# JDM2_w_MOSFET_2.net
KiCad netlist of a schematic drawn in EAGLE
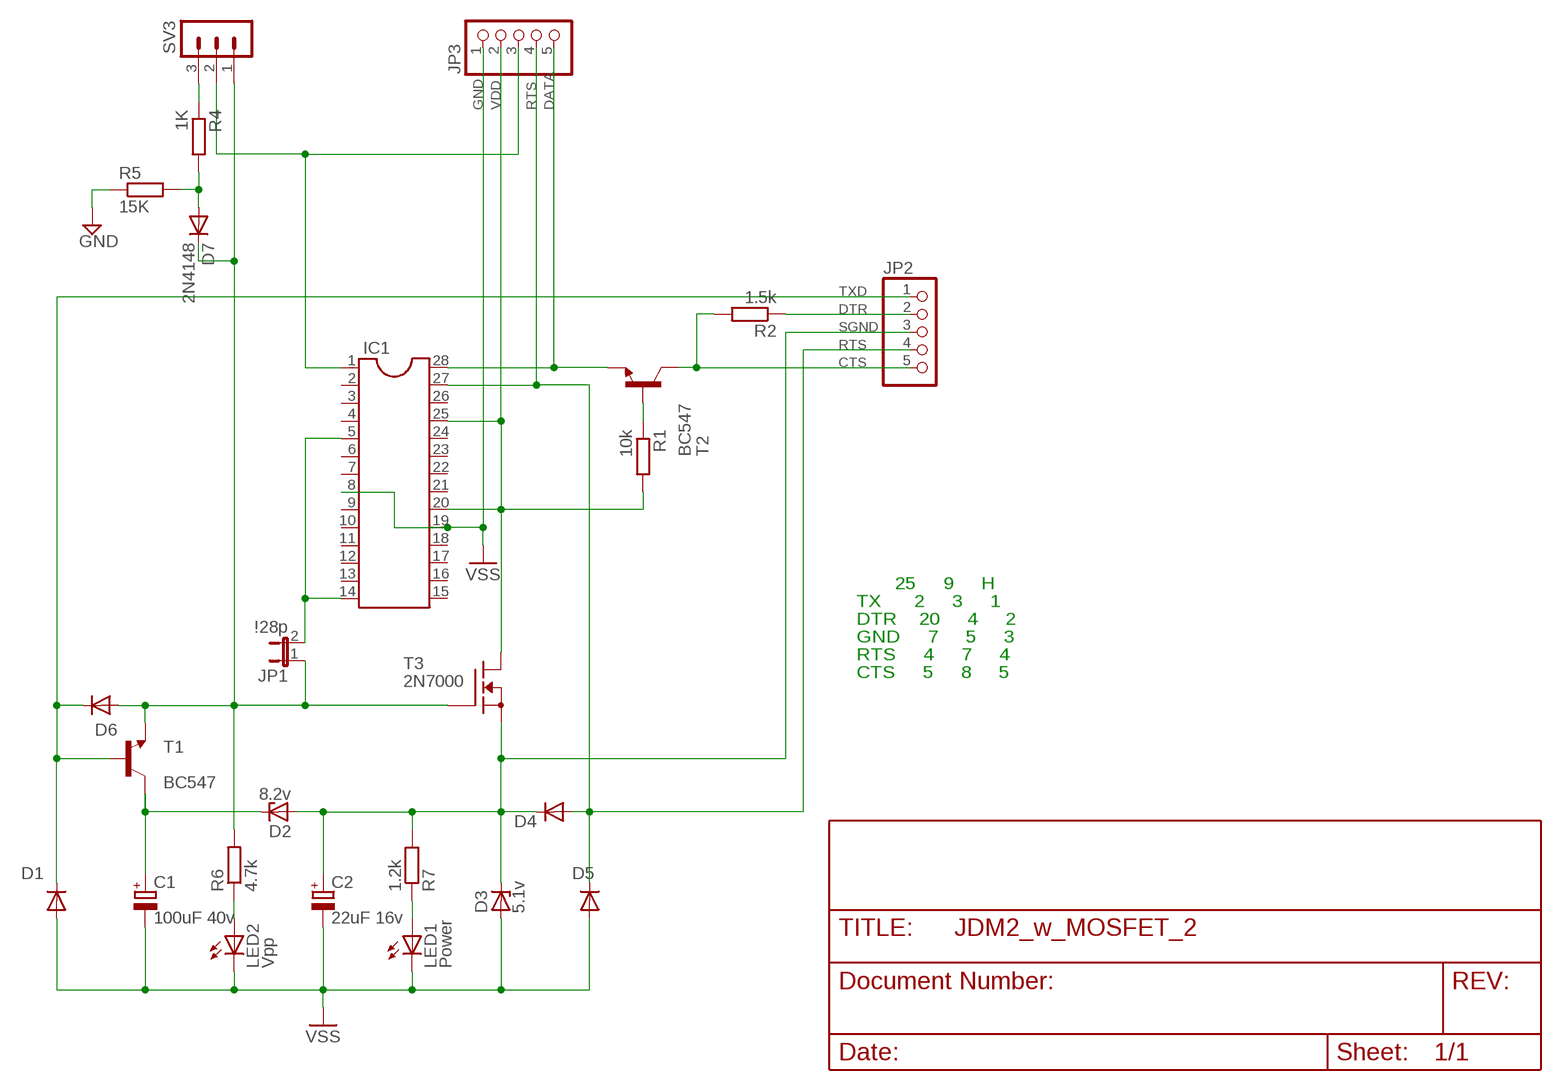
[diagram p0: schematic, sheet 1]

(export (version "E")
  (design (tool "Eeschema 10.0.6"))
  (components
    (comp (ref "C1")
      (value "100uF 40v")
      (footprint "eagle-import:E2,5-6")
      (libsource (lib "eagle-import") (part "CPOL-EUE2.5-6"))
    )
    (comp (ref "C2")
      (value "22uF 16v")
      (footprint "eagle-import:E2,5-6")
      (libsource (lib "eagle-import") (part "CPOL-EUE2.5-6"))
    )
    (comp (ref "D1")
      (value "1N4148")
      (footprint "eagle-import:DO35-7")
      (libsource (lib "eagle-import") (part "2N41487"))
    )
    (comp (ref "D2")
      (value "8.2v")
      (footprint "eagle-import:DO35Z7")
      (libsource (lib "eagle-import") (part "Z-DIODEZ7"))
    )
    (comp (ref "D3")
      (value "5.1v")
      (footprint "eagle-import:DO35Z7")
      (libsource (lib "eagle-import") (part "Z-DIODEZ7"))
    )
    (comp (ref "D4")
      (value "1N4148")
      (footprint "eagle-import:DO35-5")
      (libsource (lib "eagle-import") (part "2N41485"))
    )
    (comp (ref "D5")
      (value "1N4148")
      (footprint "eagle-import:DO35-5")
      (libsource (lib "eagle-import") (part "2N41485"))
    )
    (comp (ref "D6")
      (value "1N4148")
      (footprint "eagle-import:DO35-5")
      (libsource (lib "eagle-import") (part "2N41485"))
    )
    (comp (ref "D7")
      (value "2N4148")
      (footprint "eagle-import:DO35-5")
      (libsource (lib "eagle-import") (part "2N41485"))
    )
    (comp (ref "IC1")
      (value "DIL28-3")
      (footprint "eagle-import:DIL28-3")
      (libsource (lib "eagle-import") (part "DIL28-3"))
    )
    (comp (ref "JP1")
      (value "\\!28p")
      (footprint "eagle-import:JP1")
      (libsource (lib "eagle-import") (part "JP1E"))
    )
    (comp (ref "JP2")
      (value "PINHD-1X5")
      (footprint "eagle-import:1X05")
      (libsource (lib "eagle-import") (part "PINHD-1X5"))
    )
    (comp (ref "JP3")
      (value "PINHD-1X5")
      (footprint "eagle-import:1X05")
      (libsource (lib "eagle-import") (part "PINHD-1X5"))
    )
    (comp (ref "LED1")
      (value "Power")
      (footprint "eagle-import:LED5MM")
      (libsource (lib "eagle-import") (part "LED"))
    )
    (comp (ref "LED2")
      (value "Vpp")
      (footprint "eagle-import:LED5MM")
      (libsource (lib "eagle-import") (part "LED"))
    )
    (comp (ref "R1")
      (value "10k")
      (footprint "eagle-import:0204_7")
      (libsource (lib "eagle-import") (part "R-EU_0204/7"))
    )
    (comp (ref "R2")
      (value "1.5k")
      (footprint "eagle-import:0204_7")
      (libsource (lib "eagle-import") (part "R-EU_0204/7"))
    )
    (comp (ref "R4")
      (value "1K")
      (footprint "eagle-import:0204_7")
      (libsource (lib "eagle-import") (part "R-EU_0204/7"))
    )
    (comp (ref "R5")
      (value "15K")
      (footprint "eagle-import:0204_5")
      (libsource (lib "eagle-import") (part "R-EU_0204/5"))
    )
    (comp (ref "R6")
      (value "4.7k")
      (footprint "eagle-import:0204_7")
      (libsource (lib "eagle-import") (part "R-EU_0204/7"))
    )
    (comp (ref "R7")
      (value "1.2k")
      (footprint "eagle-import:0204_7")
      (libsource (lib "eagle-import") (part "R-EU_0204/7"))
    )
    (comp (ref "SV3")
      (value "MA03-1")
      (footprint "eagle-import:MA03-1")
      (libsource (lib "eagle-import") (part "MA03-1"))
    )
    (comp (ref "T1")
      (value "BC547")
      (footprint "eagle-import:TO92-CBE")
      (libsource (lib "eagle-import") (part "BC547"))
    )
    (comp (ref "T2")
      (value "BC547")
      (footprint "eagle-import:TO92-CBE")
      (libsource (lib "eagle-import") (part "BC547"))
    )
    (comp (ref "T3")
      (value "2N7000")
      (footprint "eagle-import:TO92")
      (libsource (lib "eagle-import") (part "2N7000"))
    )
  )
  (nets
    (net (code "1") (name "/CTS") (class "Default")
      (node (ref "JP2") (pin "5") (pinfunction "5_5") (pintype "passive"))
      (node (ref "R2") (pin "2") (pinfunction "2_2") (pintype "passive"))
      (node (ref "T2") (pin "C") (pinfunction "C_C") (pintype "passive"))
    )
    (net (code "2") (name "/DATA") (class "Default")
      (node (ref "IC1") (pin "28") (pinfunction "28_28") (pintype "passive"))
      (node (ref "JP3") (pin "5") (pinfunction "5_5") (pintype "passive"))
      (node (ref "T2") (pin "E") (pinfunction "E_E") (pintype "passive"))
    )
    (net (code "3") (name "/DTR") (class "Default")
      (node (ref "JP2") (pin "2") (pinfunction "2_2") (pintype "passive"))
      (node (ref "R2") (pin "1") (pinfunction "1_1") (pintype "passive"))
    )
    (net (code "4") (name "/RTS") (class "Default")
      (node (ref "D4") (pin "A") (pinfunction "A_A") (pintype "passive"))
      (node (ref "D5") (pin "C") (pinfunction "C_C") (pintype "passive"))
      (node (ref "IC1") (pin "27") (pinfunction "27_27") (pintype "passive"))
      (node (ref "JP2") (pin "4") (pinfunction "4_4") (pintype "passive"))
      (node (ref "JP3") (pin "4") (pinfunction "4_4") (pintype "passive"))
    )
    (net (code "5") (name "/SGND") (class "Default")
      (node (ref "C2") (pin "+") (pinfunction "+_+") (pintype "passive"))
      (node (ref "D2") (pin "A") (pinfunction "A_A") (pintype "passive"))
      (node (ref "D3") (pin "C") (pinfunction "C_C") (pintype "passive"))
      (node (ref "D4") (pin "C") (pinfunction "C_C") (pintype "passive"))
      (node (ref "JP2") (pin "3") (pinfunction "3_3") (pintype "passive"))
      (node (ref "R7") (pin "2") (pinfunction "2_2") (pintype "passive"))
      (node (ref "T3") (pin "1") (pinfunction "S_1") (pintype "passive"))
    )
    (net (code "6") (name "/TXD") (class "Default")
      (node (ref "D1") (pin "C") (pinfunction "C_C") (pintype "passive"))
      (node (ref "D6") (pin "C") (pinfunction "C_C") (pintype "passive"))
      (node (ref "JP2") (pin "1") (pinfunction "1_1") (pintype "passive"))
      (node (ref "T1") (pin "B") (pinfunction "B_B") (pintype "passive"))
    )
    (net (code "7") (name "/VDD") (class "Default")
      (node (ref "IC1") (pin "20") (pinfunction "20_20") (pintype "passive"))
      (node (ref "IC1") (pin "25") (pinfunction "25_25") (pintype "passive"))
      (node (ref "JP3") (pin "2") (pinfunction "2_2") (pintype "passive"))
      (node (ref "R1") (pin "2") (pinfunction "2_2") (pintype "passive"))
      (node (ref "T3") (pin "3") (pinfunction "D_3") (pintype "passive"))
    )
    (net (code "8") (name "GND") (class "Default")
      (node (ref "C1") (pin "-") (pinfunction "-_-") (pintype "passive"))
      (node (ref "C2") (pin "-") (pinfunction "-_-") (pintype "passive"))
      (node (ref "D1") (pin "A") (pinfunction "A_A") (pintype "passive"))
      (node (ref "D3") (pin "A") (pinfunction "A_A") (pintype "passive"))
      (node (ref "D5") (pin "A") (pinfunction "A_A") (pintype "passive"))
      (node (ref "IC1") (pin "19") (pinfunction "19_19") (pintype "passive"))
      (node (ref "IC1") (pin "8") (pinfunction "8_8") (pintype "passive"))
      (node (ref "JP3") (pin "1") (pinfunction "1_1") (pintype "passive"))
      (node (ref "LED1") (pin "K") (pinfunction "C_K") (pintype "passive"))
      (node (ref "LED2") (pin "K") (pinfunction "C_K") (pintype "passive"))
      (node (ref "R5") (pin "1") (pinfunction "1_1") (pintype "passive"))
    )
    (net (code "9") (name "Net-(C1-Pad+)") (class "Default")
      (node (ref "C1") (pin "+") (pinfunction "+_+") (pintype "passive"))
      (node (ref "D2") (pin "C") (pinfunction "C_C") (pintype "passive"))
      (node (ref "T1") (pin "C") (pinfunction "C_C") (pintype "passive"))
    )
    (net (code "10") (name "Net-(D7-PadA)") (class "Default")
      (node (ref "D7") (pin "A") (pinfunction "A_A") (pintype "passive"))
      (node (ref "R4") (pin "2") (pinfunction "2_2") (pintype "passive"))
      (node (ref "R5") (pin "2") (pinfunction "2_2") (pintype "passive"))
    )
    (net (code "11") (name "Net-(IC1-Pad1)") (class "Default")
      (node (ref "IC1") (pin "1") (pinfunction "1_1") (pintype "passive"))
      (node (ref "JP3") (pin "3") (pinfunction "3_3") (pintype "passive"))
      (node (ref "SV3") (pin "2") (pinfunction "2_2") (pintype "passive"))
    )
    (net (code "12") (name "Net-(IC1-Pad14)") (class "Default")
      (node (ref "IC1") (pin "14") (pinfunction "14_14") (pintype "passive"))
      (node (ref "IC1") (pin "5") (pinfunction "5_5") (pintype "passive"))
      (node (ref "JP1") (pin "2") (pinfunction "2_2") (pintype "passive"))
    )
    (net (code "13") (name "Net-(LED1-PadA)") (class "Default")
      (node (ref "LED1") (pin "A") (pinfunction "A_A") (pintype "passive"))
      (node (ref "R7") (pin "1") (pinfunction "1_1") (pintype "passive"))
    )
    (net (code "14") (name "Net-(LED2-PadA)") (class "Default")
      (node (ref "LED2") (pin "A") (pinfunction "A_A") (pintype "passive"))
      (node (ref "R6") (pin "1") (pinfunction "1_1") (pintype "passive"))
    )
    (net (code "15") (name "Net-(R1-Pad1)") (class "Default")
      (node (ref "R1") (pin "1") (pinfunction "1_1") (pintype "passive"))
      (node (ref "T2") (pin "B") (pinfunction "B_B") (pintype "passive"))
    )
    (net (code "16") (name "Net-(R4-Pad1)") (class "Default")
      (node (ref "R4") (pin "1") (pinfunction "1_1") (pintype "passive"))
      (node (ref "SV3") (pin "3") (pinfunction "3_3") (pintype "passive"))
    )
    (net (code "17") (name "Net-(T3-G)") (class "Default")
      (node (ref "D6") (pin "A") (pinfunction "A_A") (pintype "passive"))
      (node (ref "D7") (pin "C") (pinfunction "C_C") (pintype "passive"))
      (node (ref "JP1") (pin "1") (pinfunction "1_1") (pintype "passive"))
      (node (ref "R6") (pin "2") (pinfunction "2_2") (pintype "passive"))
      (node (ref "SV3") (pin "1") (pinfunction "1_1") (pintype "passive"))
      (node (ref "T1") (pin "E") (pinfunction "E_E") (pintype "passive"))
      (node (ref "T3") (pin "2") (pinfunction "G_2") (pintype "passive"))
    )
    (net (code "18") (name "unconnected-(IC1-Pad2)") (class "Default")
      (node (ref "IC1") (pin "2") (pinfunction "2_2") (pintype "passive"))
    )
    (net (code "19") (name "unconnected-(IC1-Pad3)") (class "Default")
      (node (ref "IC1") (pin "3") (pinfunction "3_3") (pintype "passive"))
    )
    (net (code "20") (name "unconnected-(IC1-Pad4)") (class "Default")
      (node (ref "IC1") (pin "4") (pinfunction "4_4") (pintype "passive"))
    )
    (net (code "21") (name "unconnected-(IC1-Pad6)") (class "Default")
      (node (ref "IC1") (pin "6") (pinfunction "6_6") (pintype "passive"))
    )
    (net (code "22") (name "unconnected-(IC1-Pad7)") (class "Default")
      (node (ref "IC1") (pin "7") (pinfunction "7_7") (pintype "passive"))
    )
    (net (code "23") (name "unconnected-(IC1-Pad9)") (class "Default")
      (node (ref "IC1") (pin "9") (pinfunction "9_9") (pintype "passive"))
    )
    (net (code "24") (name "unconnected-(IC1-Pad10)") (class "Default")
      (node (ref "IC1") (pin "10") (pinfunction "10_10") (pintype "passive"))
    )
    (net (code "25") (name "unconnected-(IC1-Pad11)") (class "Default")
      (node (ref "IC1") (pin "11") (pinfunction "11_11") (pintype "passive"))
    )
    (net (code "26") (name "unconnected-(IC1-Pad12)") (class "Default")
      (node (ref "IC1") (pin "12") (pinfunction "12_12") (pintype "passive"))
    )
    (net (code "27") (name "unconnected-(IC1-Pad13)") (class "Default")
      (node (ref "IC1") (pin "13") (pinfunction "13_13") (pintype "passive"))
    )
    (net (code "28") (name "unconnected-(IC1-Pad15)") (class "Default")
      (node (ref "IC1") (pin "15") (pinfunction "15_15") (pintype "passive"))
    )
    (net (code "29") (name "unconnected-(IC1-Pad16)") (class "Default")
      (node (ref "IC1") (pin "16") (pinfunction "16_16") (pintype "passive"))
    )
    (net (code "30") (name "unconnected-(IC1-Pad17)") (class "Default")
      (node (ref "IC1") (pin "17") (pinfunction "17_17") (pintype "passive"))
    )
    (net (code "31") (name "unconnected-(IC1-Pad18)") (class "Default")
      (node (ref "IC1") (pin "18") (pinfunction "18_18") (pintype "passive"))
    )
    (net (code "32") (name "unconnected-(IC1-Pad21)") (class "Default")
      (node (ref "IC1") (pin "21") (pinfunction "21_21") (pintype "passive"))
    )
    (net (code "33") (name "unconnected-(IC1-Pad22)") (class "Default")
      (node (ref "IC1") (pin "22") (pinfunction "22_22") (pintype "passive"))
    )
    (net (code "34") (name "unconnected-(IC1-Pad23)") (class "Default")
      (node (ref "IC1") (pin "23") (pinfunction "23_23") (pintype "passive"))
    )
    (net (code "35") (name "unconnected-(IC1-Pad24)") (class "Default")
      (node (ref "IC1") (pin "24") (pinfunction "24_24") (pintype "passive"))
    )
    (net (code "36") (name "unconnected-(IC1-Pad26)") (class "Default")
      (node (ref "IC1") (pin "26") (pinfunction "26_26") (pintype "passive"))
    )
  )
)
